# Main.net
KiCad netlist of a schematic drawn in Altium Designer
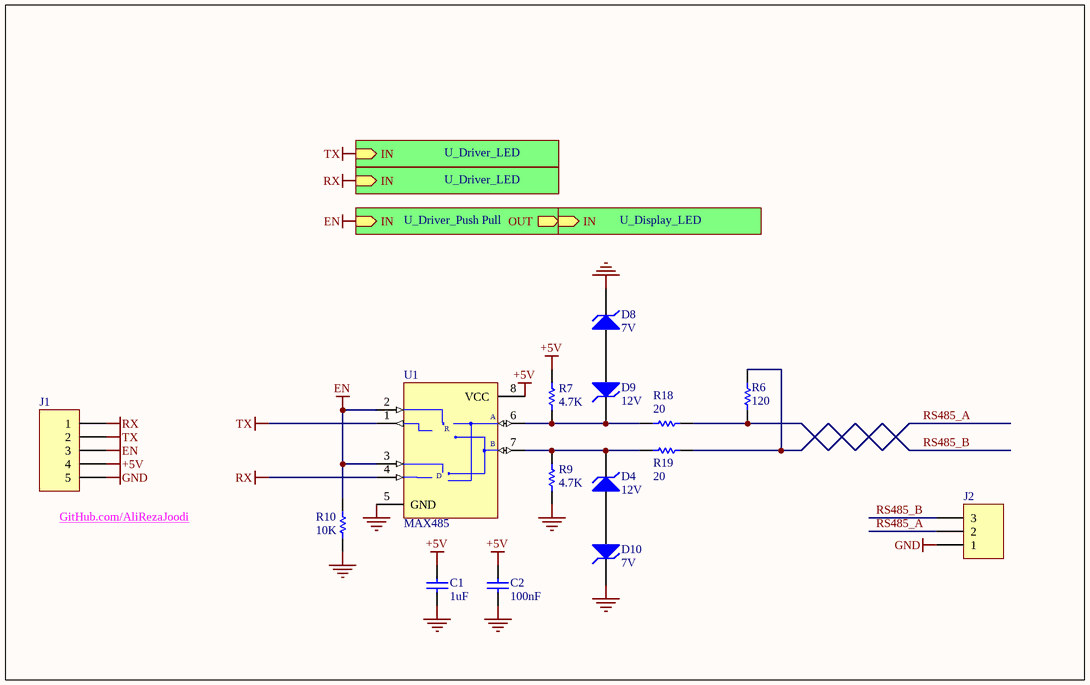
[diagram p0: Main.SchDoc]

(export (version "E")
  (design (tool "Eeschema 10.0.6"))
  (components
    (comp (ref "C1")
      (value "1uF")
      (footprint "0805")
      (description "Capacitor")
      (fields (field (name "MANUFACTURER") "Generic Components") (field (name "PUBLISHER") "Altium Limited"))
      (libsource (lib "Miscellaneous Devices") (part "Cap"))
    )
    (comp (ref "C2")
      (value "100nF")
      (footprint "0805")
      (description "Capacitor")
      (fields (field (name "MANUFACTURER") "Generic Components") (field (name "PUBLISHER") "Altium Limited"))
      (libsource (lib "Miscellaneous Devices") (part "Cap"))
    )
    (comp (ref "D4")
      (value "12V")
      (footprint "ZENER_DIODE")
      (description "Zener Diode")
      (fields (field (name "MANUFACTURER") "Generic Components") (field (name "PUBLISHER") "Altium Limited"))
      (libsource (lib "Miscellaneous Devices") (part "D Zener"))
    )
    (comp (ref "D8")
      (value "7V")
      (footprint "ZENER_DIODE")
      (description "Zener Diode")
      (fields (field (name "MANUFACTURER") "Generic Components") (field (name "PUBLISHER") "Altium Limited"))
      (libsource (lib "Miscellaneous Devices") (part "D Zener"))
    )
    (comp (ref "D9")
      (value "12V")
      (footprint "ZENER_DIODE")
      (description "Zener Diode")
      (fields (field (name "MANUFACTURER") "Generic Components") (field (name "PUBLISHER") "Altium Limited"))
      (libsource (lib "Miscellaneous Devices") (part "D Zener"))
    )
    (comp (ref "D10")
      (value "7V")
      (footprint "ZENER_DIODE")
      (description "Zener Diode")
      (fields (field (name "MANUFACTURER") "Generic Components") (field (name "PUBLISHER") "Altium Limited"))
      (libsource (lib "Miscellaneous Devices") (part "D Zener"))
    )
    (comp (ref "J1")
      (value "Header 5")
      (footprint "HDR1X5")
      (description "Header, 5-Pin")
      (fields (field (name "MANUFACTURER") "Generic Components") (field (name "PUBLISHER") "Altium Limited"))
      (libsource (lib "Miscellaneous Connectors") (part "Header 5"))
    )
    (comp (ref "J2")
      (value "Header 3")
      (footprint "HDR1X3")
      (description "Header, 3-Pin")
      (fields (field (name "MANUFACTURER") "Generic Components") (field (name "PUBLISHER") "Altium Limited"))
      (libsource (lib "Miscellaneous Connectors") (part "Header 3"))
    )
    (comp (ref "R6")
      (value "120")
      (footprint "0805")
      (description "Resistor")
      (fields (field (name "PUBLISHER") "Altium Limited"))
      (libsource (lib "Miscellaneous Devices") (part "Res1"))
    )
    (comp (ref "R7")
      (value "4.7K")
      (footprint "0805")
      (description "Resistor")
      (fields (field (name "PUBLISHER") "Altium Limited"))
      (libsource (lib "Miscellaneous Devices") (part "Res1"))
    )
    (comp (ref "R9")
      (value "4.7K")
      (footprint "0805")
      (description "Resistor")
      (fields (field (name "PUBLISHER") "Altium Limited"))
      (libsource (lib "Miscellaneous Devices") (part "Res1"))
    )
    (comp (ref "R10")
      (value "10K")
      (footprint "0805")
      (description "Resistor")
      (fields (field (name "PUBLISHER") "Altium Limited"))
      (libsource (lib "Miscellaneous Devices") (part "Res1"))
    )
    (comp (ref "R18")
      (value "20")
      (footprint "0805")
      (description "Resistor")
      (fields (field (name "PUBLISHER") "Altium Limited"))
      (libsource (lib "Miscellaneous Devices") (part "Res1"))
    )
    (comp (ref "R19")
      (value "20")
      (footprint "0805")
      (description "Resistor")
      (fields (field (name "PUBLISHER") "Altium Limited"))
      (libsource (lib "Miscellaneous Devices") (part "Res1"))
    )
    (comp (ref "U1")
      (value "MAX485")
      (footprint "SOP127P636-8N")
      (description "Low-Power, Slew-Rate-Limited RS-485/RS-422 Transceiver")
      (fields (field (name "PUBLISHER") "Altium Limited"))
      (libsource (lib "Maxim Communication Transceiver") (part "MAX485CPA"))
    )
  )
  (nets
    (net (code "1") (name "+5V") (class "Default")
      (node (ref "C1") (pin "2") (pinfunction "2_2") (pintype "passive"))
      (node (ref "C2") (pin "2") (pinfunction "2_2") (pintype "passive"))
      (node (ref "J1") (pin "4") (pinfunction "4_4") (pintype "passive"))
      (node (ref "R7") (pin "1") (pinfunction "1_1") (pintype "passive"))
      (node (ref "U1") (pin "8") (pinfunction "VCC_8") (pintype "power_in"))
    )
    (net (code "3") (name "/RS485_A") (class "Default")
      (node (ref "J2") (pin "2") (pinfunction "2_2") (pintype "passive"))
      (node (ref "R18") (pin "1") (pinfunction "1_1") (pintype "passive"))
      (node (ref "R6") (pin "1") (pinfunction "1_1") (pintype "passive"))
    )
    (net (code "4") (name "/RS485_B") (class "Default")
      (node (ref "J2") (pin "3") (pinfunction "3_3") (pintype "passive"))
      (node (ref "R19") (pin "1") (pinfunction "1_1") (pintype "passive"))
      (node (ref "R6") (pin "2") (pinfunction "2_2") (pintype "passive"))
    )
    (net (code "5") (name "EN") (class "Default")
      (node (ref "J1") (pin "3") (pinfunction "3_3") (pintype "passive"))
      (node (ref "R10") (pin "2") (pinfunction "2_2") (pintype "passive"))
      (node (ref "U1") (pin "2") (pinfunction "~{RE}_2") (pintype "input"))
      (node (ref "U1") (pin "3") (pinfunction "DE_3") (pintype "input"))
    )
    (net (code "6") (name "GND") (class "Default")
      (node (ref "C1") (pin "1") (pinfunction "1_1") (pintype "passive"))
      (node (ref "C2") (pin "1") (pinfunction "1_1") (pintype "passive"))
      (node (ref "D10") (pin "2") (pinfunction "K_2") (pintype "passive"))
      (node (ref "D8") (pin "2") (pinfunction "K_2") (pintype "passive"))
      (node (ref "J1") (pin "5") (pinfunction "5_5") (pintype "passive"))
      (node (ref "J2") (pin "1") (pinfunction "1_1") (pintype "passive"))
      (node (ref "R10") (pin "1") (pinfunction "1_1") (pintype "passive"))
      (node (ref "R9") (pin "2") (pinfunction "2_2") (pintype "passive"))
      (node (ref "U1") (pin "5") (pinfunction "GND_5") (pintype "power_in"))
    )
    (net (code "7") (name "Net-(D4-K)") (class "Default")
      (node (ref "D4") (pin "2") (pinfunction "K_2") (pintype "passive"))
      (node (ref "R19") (pin "2") (pinfunction "2_2") (pintype "passive"))
      (node (ref "R9") (pin "1") (pinfunction "1_1") (pintype "passive"))
      (node (ref "U1") (pin "7") (pinfunction "B_7") (pintype "bidirectional"))
    )
    (net (code "8") (name "Net-(D8-A)") (class "Default")
      (node (ref "D8") (pin "1") (pinfunction "A_1") (pintype "passive"))
      (node (ref "D9") (pin "1") (pinfunction "A_1") (pintype "passive"))
    )
    (net (code "9") (name "Net-(D9-K)") (class "Default")
      (node (ref "D9") (pin "2") (pinfunction "K_2") (pintype "passive"))
      (node (ref "R18") (pin "2") (pinfunction "2_2") (pintype "passive"))
      (node (ref "R7") (pin "2") (pinfunction "2_2") (pintype "passive"))
      (node (ref "U1") (pin "6") (pinfunction "A_6") (pintype "bidirectional"))
    )
    (net (code "10") (name "Net-(D10-A)") (class "Default")
      (node (ref "D10") (pin "1") (pinfunction "A_1") (pintype "passive"))
      (node (ref "D4") (pin "1") (pinfunction "A_1") (pintype "passive"))
    )
    (net (code "11") (name "RX") (class "Default")
      (node (ref "J1") (pin "1") (pinfunction "1_1") (pintype "passive"))
      (node (ref "U1") (pin "4") (pinfunction "DI_4") (pintype "input"))
    )
    (net (code "12") (name "TX") (class "Default")
      (node (ref "J1") (pin "2") (pinfunction "2_2") (pintype "passive"))
      (node (ref "U1") (pin "1") (pinfunction "RO_1") (pintype "output"))
    )
  )
)
